# usb-seal.net
KiCad netlist of a schematic drawn in EasyEDA Pro
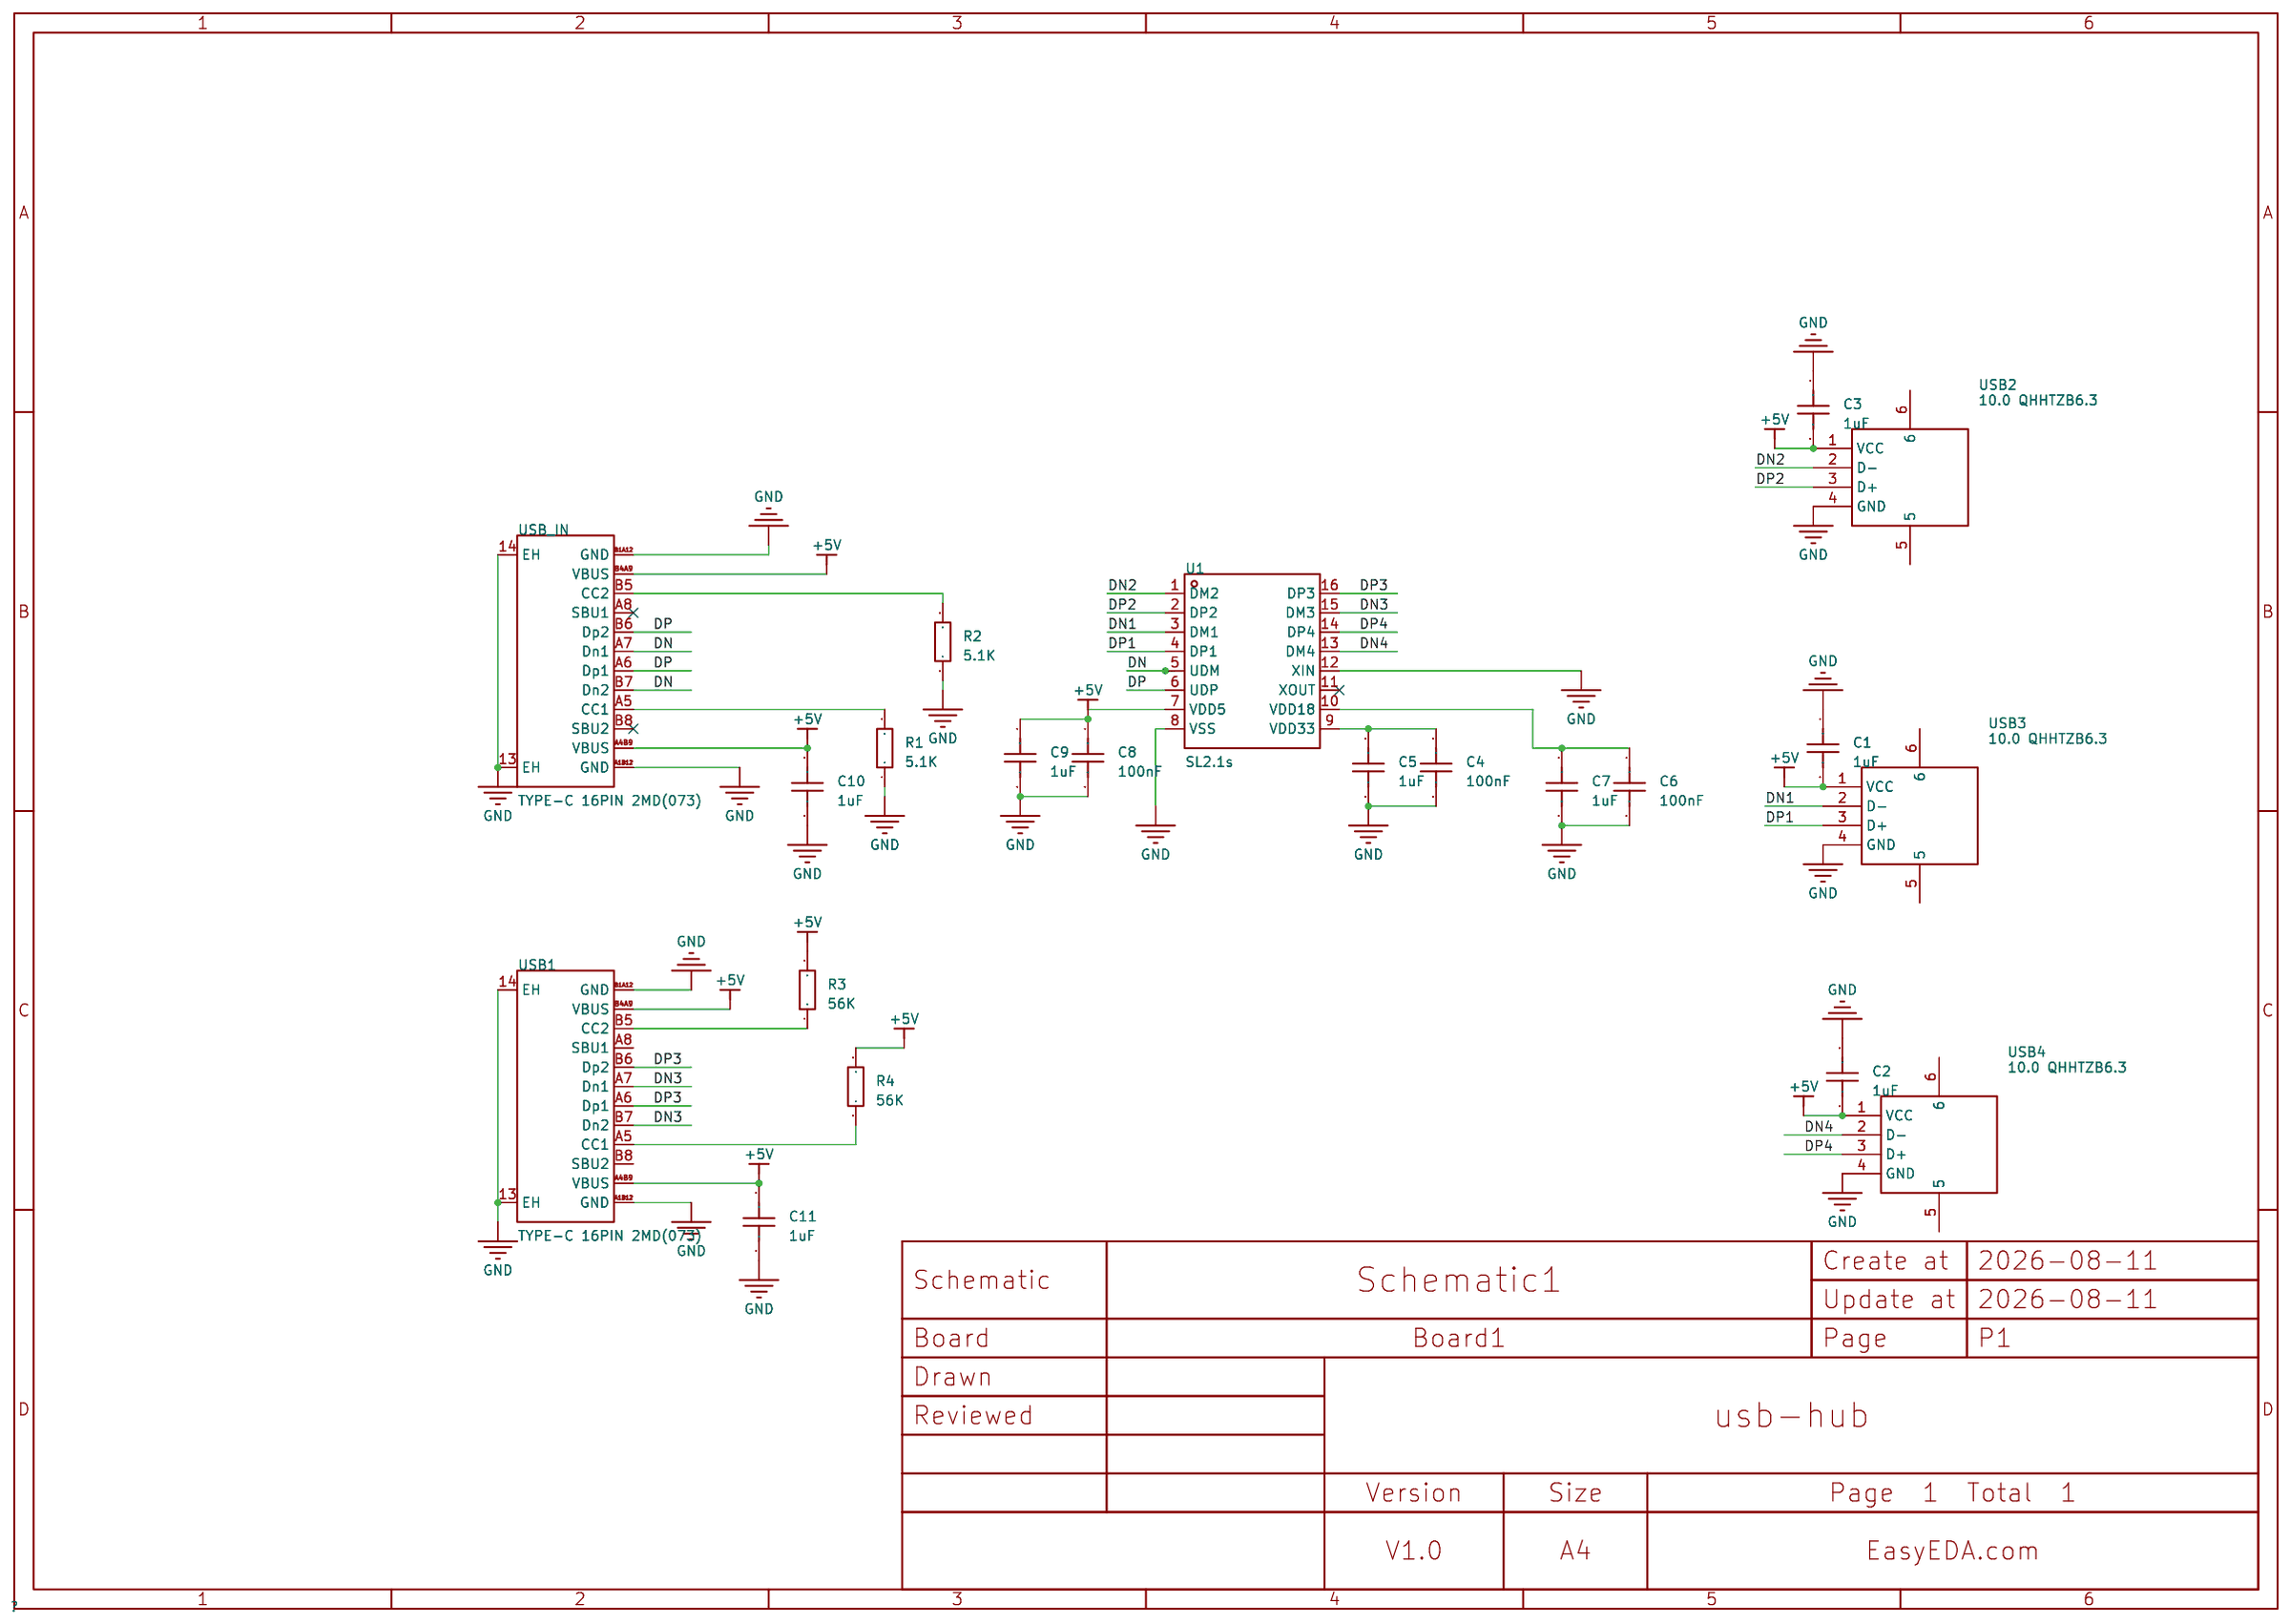
[diagram p0: schematic sheet]

(export (version "E")
  (design (tool "Eeschema 10.0.6"))
  (components
    (comp (ref "C1")
      (value "1uF")
      (footprint "easyedapro:C0603")
      (libsource (lib "easyedapro") (part "CAP_OLD"))
    )
    (comp (ref "C2")
      (value "1uF")
      (footprint "easyedapro:C0603")
      (libsource (lib "easyedapro") (part "CAP_OLD"))
    )
    (comp (ref "C3")
      (value "1uF")
      (footprint "easyedapro:C0603")
      (libsource (lib "easyedapro") (part "CAP_OLD"))
    )
    (comp (ref "C4")
      (value "100nF")
      (footprint "easyedapro:C0603")
      (libsource (lib "easyedapro") (part "CAP_OLD"))
    )
    (comp (ref "C5")
      (value "1uF")
      (footprint "easyedapro:C0603")
      (libsource (lib "easyedapro") (part "CAP_OLD"))
    )
    (comp (ref "C6")
      (value "100nF")
      (footprint "easyedapro:C0603")
      (libsource (lib "easyedapro") (part "CAP_OLD"))
    )
    (comp (ref "C7")
      (value "1uF")
      (footprint "easyedapro:C0603")
      (libsource (lib "easyedapro") (part "CAP_OLD"))
    )
    (comp (ref "C8")
      (value "100nF")
      (footprint "easyedapro:C0603")
      (libsource (lib "easyedapro") (part "CAP_OLD"))
    )
    (comp (ref "C9")
      (value "1uF")
      (footprint "easyedapro:C0603")
      (libsource (lib "easyedapro") (part "CAP_OLD"))
    )
    (comp (ref "C10")
      (value "1uF")
      (footprint "easyedapro:C0603")
      (libsource (lib "easyedapro") (part "CAP_OLD"))
    )
    (comp (ref "C11")
      (value "1uF")
      (footprint "easyedapro:C0603")
      (libsource (lib "easyedapro") (part "CAP_OLD"))
    )
    (comp (ref "R1")
      (value "5.1K")
      (footprint "easyedapro:R0603")
      (libsource (lib "easyedapro") (part "Res"))
    )
    (comp (ref "R2")
      (value "5.1K")
      (footprint "easyedapro:R0603")
      (libsource (lib "easyedapro") (part "Res"))
    )
    (comp (ref "R3") (value "56K") (footprint "easyedapro:R0603") (libsource (lib "easyedapro") (part "Res")))
    (comp (ref "R4") (value "56K") (footprint "easyedapro:R0603") (libsource (lib "easyedapro") (part "Res")))
    (comp (ref "U1")
      (value "SL2.1s")
      (footprint "easyedapro:SSOP-16_L4.6-W2.6-P0.53-LS4.0-BL")
      (fields (field (name "Manufacturer") "CoreChips(和芯润德)"))
      (libsource (lib "easyedapro") (part "SL2.1S"))
    )
    (comp (ref "USB1")
      (value "TYPE-C 16PIN 2MD(073)")
      (footprint "easyedapro:USB-C-SMD_TYPE-C-16PIN-2MD-073")
      (fields (field (name "Manufacturer") "SHOU HAN(首韩)"))
      (libsource (lib "easyedapro") (part "TYPE-C 16PIN 2MD(073)"))
    )
    (comp (ref "USB2")
      (value "10.0 QHHTZB6.3")
      (footprint "easyedapro:USB-A-TH_10.0QHHTZB6.3")
      (fields (field (name "Manufacturer") "SHOU HAN(首韩)"))
      (libsource (lib "easyedapro") (part "10.0 QHHTZB6.3"))
    )
    (comp (ref "USB3")
      (value "10.0 QHHTZB6.3")
      (footprint "easyedapro:USB-A-TH_10.0QHHTZB6.3")
      (fields (field (name "Manufacturer") "SHOU HAN(首韩)"))
      (libsource (lib "easyedapro") (part "10.0 QHHTZB6.3"))
    )
    (comp (ref "USB4")
      (value "10.0 QHHTZB6.3")
      (footprint "easyedapro:USB-A-TH_10.0QHHTZB6.3")
      (fields (field (name "Manufacturer") "SHOU HAN(首韩)"))
      (libsource (lib "easyedapro") (part "10.0 QHHTZB6.3"))
    )
    (comp (ref "USB_IN")
      (value "TYPE-C 16PIN 2MD(073)")
      (footprint "easyedapro:USB-C-SMD_TYPE-C-16PIN-2MD-073")
      (fields (field (name "Manufacturer") "SHOU HAN(首韩)"))
      (libsource (lib "easyedapro") (part "TYPE-C 16PIN 2MD(073)"))
    )
  )
  (nets
    (net (code "1") (name "+5V") (class "Default")
      (node (ref "C1") (pin "2") (pinfunction "2_2") (pintype "input"))
      (node (ref "C10") (pin "2") (pinfunction "2_2") (pintype "input"))
      (node (ref "C11") (pin "2") (pinfunction "2_2") (pintype "input"))
      (node (ref "C2") (pin "2") (pinfunction "2_2") (pintype "input"))
      (node (ref "C3") (pin "2") (pinfunction "2_2") (pintype "input"))
      (node (ref "C8") (pin "1") (pinfunction "1_1") (pintype "input"))
      (node (ref "C9") (pin "1") (pinfunction "1_1") (pintype "input"))
      (node (ref "R3") (pin "2") (pinfunction "2_2") (pintype "input"))
      (node (ref "R4") (pin "2") (pinfunction "2_2") (pintype "input"))
      (node (ref "U1") (pin "7") (pinfunction "VDD5_7") (pintype "unspecified"))
      (node (ref "USB1") (pin "A4B9") (pinfunction "VBUS_A4B9") (pintype "unspecified"))
      (node (ref "USB1") (pin "B4A9") (pinfunction "VBUS_B4A9") (pintype "unspecified"))
      (node (ref "USB2") (pin "1") (pinfunction "VCC_1") (pintype "unspecified"))
      (node (ref "USB3") (pin "1") (pinfunction "VCC_1") (pintype "unspecified"))
      (node (ref "USB4") (pin "1") (pinfunction "VCC_1") (pintype "unspecified"))
      (node (ref "USB_IN") (pin "A4B9") (pinfunction "VBUS_A4B9") (pintype "unspecified"))
      (node (ref "USB_IN") (pin "B4A9") (pinfunction "VBUS_B4A9") (pintype "unspecified"))
    )
    (net (code "2") (name "/DN") (class "Default")
      (node (ref "U1") (pin "5") (pinfunction "UDM_5") (pintype "unspecified"))
      (node (ref "USB_IN") (pin "A7") (pinfunction "Dn1_A7") (pintype "unspecified"))
      (node (ref "USB_IN") (pin "B7") (pinfunction "Dn2_B7") (pintype "unspecified"))
    )
    (net (code "3") (name "/DN1") (class "Default")
      (node (ref "U1") (pin "3") (pinfunction "DM1_3") (pintype "unspecified"))
      (node (ref "USB3") (pin "2") (pinfunction "D-_2") (pintype "unspecified"))
    )
    (net (code "4") (name "/DN2") (class "Default")
      (node (ref "U1") (pin "1") (pinfunction "DM2_1") (pintype "unspecified"))
      (node (ref "USB2") (pin "2") (pinfunction "D-_2") (pintype "unspecified"))
    )
    (net (code "5") (name "/DN3") (class "Default")
      (node (ref "U1") (pin "15") (pinfunction "DM3_15") (pintype "unspecified"))
      (node (ref "USB1") (pin "A7") (pinfunction "Dn1_A7") (pintype "unspecified"))
      (node (ref "USB1") (pin "B7") (pinfunction "Dn2_B7") (pintype "unspecified"))
    )
    (net (code "6") (name "/DN4") (class "Default")
      (node (ref "U1") (pin "13") (pinfunction "DM4_13") (pintype "unspecified"))
      (node (ref "USB4") (pin "2") (pinfunction "D-_2") (pintype "unspecified"))
    )
    (net (code "7") (name "/DP") (class "Default")
      (node (ref "U1") (pin "6") (pinfunction "UDP_6") (pintype "unspecified"))
      (node (ref "USB_IN") (pin "A6") (pinfunction "Dp1_A6") (pintype "unspecified"))
      (node (ref "USB_IN") (pin "B6") (pinfunction "Dp2_B6") (pintype "unspecified"))
    )
    (net (code "8") (name "/DP1") (class "Default")
      (node (ref "U1") (pin "4") (pinfunction "DP1_4") (pintype "unspecified"))
      (node (ref "USB3") (pin "3") (pinfunction "D+_3") (pintype "unspecified"))
    )
    (net (code "9") (name "/DP2") (class "Default")
      (node (ref "U1") (pin "2") (pinfunction "DP2_2") (pintype "unspecified"))
      (node (ref "USB2") (pin "3") (pinfunction "D+_3") (pintype "unspecified"))
    )
    (net (code "10") (name "/DP3") (class "Default")
      (node (ref "U1") (pin "16") (pinfunction "DP3_16") (pintype "unspecified"))
      (node (ref "USB1") (pin "A6") (pinfunction "Dp1_A6") (pintype "unspecified"))
      (node (ref "USB1") (pin "B6") (pinfunction "Dp2_B6") (pintype "unspecified"))
    )
    (net (code "11") (name "/DP4") (class "Default")
      (node (ref "U1") (pin "14") (pinfunction "DP4_14") (pintype "unspecified"))
      (node (ref "USB4") (pin "3") (pinfunction "D+_3") (pintype "unspecified"))
    )
    (net (code "12") (name "GND") (class "Default")
      (node (ref "C1") (pin "1") (pinfunction "1_1") (pintype "input"))
      (node (ref "C10") (pin "1") (pinfunction "1_1") (pintype "input"))
      (node (ref "C11") (pin "1") (pinfunction "1_1") (pintype "input"))
      (node (ref "C2") (pin "1") (pinfunction "1_1") (pintype "input"))
      (node (ref "C3") (pin "1") (pinfunction "1_1") (pintype "input"))
      (node (ref "C4") (pin "2") (pinfunction "2_2") (pintype "input"))
      (node (ref "C5") (pin "2") (pinfunction "2_2") (pintype "input"))
      (node (ref "C6") (pin "2") (pinfunction "2_2") (pintype "input"))
      (node (ref "C7") (pin "2") (pinfunction "2_2") (pintype "input"))
      (node (ref "C8") (pin "2") (pinfunction "2_2") (pintype "input"))
      (node (ref "C9") (pin "2") (pinfunction "2_2") (pintype "input"))
      (node (ref "R1") (pin "1") (pinfunction "1_1") (pintype "input"))
      (node (ref "R2") (pin "1") (pinfunction "1_1") (pintype "input"))
      (node (ref "U1") (pin "12") (pinfunction "XIN_12") (pintype "unspecified"))
      (node (ref "U1") (pin "8") (pinfunction "VSS_8") (pintype "unspecified"))
      (node (ref "USB1") (pin "13") (pinfunction "EH_13") (pintype "unspecified"))
      (node (ref "USB1") (pin "14") (pinfunction "EH_14") (pintype "unspecified"))
      (node (ref "USB1") (pin "A1B12") (pinfunction "GND_A1B12") (pintype "unspecified"))
      (node (ref "USB1") (pin "B1A12") (pinfunction "GND_B1A12") (pintype "unspecified"))
      (node (ref "USB2") (pin "4") (pinfunction "GND_4") (pintype "unspecified"))
      (node (ref "USB3") (pin "4") (pinfunction "GND_4") (pintype "unspecified"))
      (node (ref "USB4") (pin "4") (pinfunction "GND_4") (pintype "unspecified"))
      (node (ref "USB_IN") (pin "13") (pinfunction "EH_13") (pintype "unspecified"))
      (node (ref "USB_IN") (pin "14") (pinfunction "EH_14") (pintype "unspecified"))
      (node (ref "USB_IN") (pin "A1B12") (pinfunction "GND_A1B12") (pintype "unspecified"))
      (node (ref "USB_IN") (pin "B1A12") (pinfunction "GND_B1A12") (pintype "unspecified"))
    )
    (net (code "13") (name "Net-(U1-VDD18)") (class "Default")
      (node (ref "C6") (pin "1") (pinfunction "1_1") (pintype "input"))
      (node (ref "C7") (pin "1") (pinfunction "1_1") (pintype "input"))
      (node (ref "U1") (pin "10") (pinfunction "VDD18_10") (pintype "unspecified"))
    )
    (net (code "14") (name "Net-(U1-VDD33)") (class "Default")
      (node (ref "C4") (pin "1") (pinfunction "1_1") (pintype "input"))
      (node (ref "C5") (pin "1") (pinfunction "1_1") (pintype "input"))
      (node (ref "U1") (pin "9") (pinfunction "VDD33_9") (pintype "unspecified"))
    )
    (net (code "15") (name "Net-(USB1-CC1)") (class "Default")
      (node (ref "R4") (pin "1") (pinfunction "1_1") (pintype "input"))
      (node (ref "USB1") (pin "A5") (pinfunction "CC1_A5") (pintype "unspecified"))
    )
    (net (code "16") (name "Net-(USB1-CC2)") (class "Default")
      (node (ref "R3") (pin "1") (pinfunction "1_1") (pintype "input"))
      (node (ref "USB1") (pin "B5") (pinfunction "CC2_B5") (pintype "unspecified"))
    )
    (net (code "17") (name "Net-(USB_IN-CC1)") (class "Default")
      (node (ref "R1") (pin "2") (pinfunction "2_2") (pintype "input"))
      (node (ref "USB_IN") (pin "A5") (pinfunction "CC1_A5") (pintype "unspecified"))
    )
    (net (code "18") (name "Net-(USB_IN-CC2)") (class "Default")
      (node (ref "R2") (pin "2") (pinfunction "2_2") (pintype "input"))
      (node (ref "USB_IN") (pin "B5") (pinfunction "CC2_B5") (pintype "unspecified"))
    )
    (net (code "19") (name "unconnected-(U1-XOUT-Pad11)") (class "Default")
      (node (ref "U1") (pin "11") (pinfunction "XOUT_11") (pintype "unspecified+no_connect"))
    )
    (net (code "20") (name "unconnected-(USB1-SBU1-PadA8)") (class "Default")
      (node (ref "USB1") (pin "A8") (pinfunction "SBU1_A8") (pintype "unspecified"))
    )
    (net (code "21") (name "unconnected-(USB1-SBU2-PadB8)") (class "Default")
      (node (ref "USB1") (pin "B8") (pinfunction "SBU2_B8") (pintype "unspecified"))
    )
    (net (code "22") (name "unconnected-(USB2-Pad5)") (class "Default")
      (node (ref "USB2") (pin "5") (pinfunction "5_5") (pintype "unspecified"))
    )
    (net (code "23") (name "unconnected-(USB2-Pad6)") (class "Default")
      (node (ref "USB2") (pin "6") (pinfunction "6_6") (pintype "unspecified"))
    )
    (net (code "24") (name "unconnected-(USB3-Pad5)") (class "Default")
      (node (ref "USB3") (pin "5") (pinfunction "5_5") (pintype "unspecified"))
    )
    (net (code "25") (name "unconnected-(USB3-Pad6)") (class "Default")
      (node (ref "USB3") (pin "6") (pinfunction "6_6") (pintype "unspecified"))
    )
    (net (code "26") (name "unconnected-(USB4-Pad5)") (class "Default")
      (node (ref "USB4") (pin "5") (pinfunction "5_5") (pintype "unspecified"))
    )
    (net (code "27") (name "unconnected-(USB4-Pad6)") (class "Default")
      (node (ref "USB4") (pin "6") (pinfunction "6_6") (pintype "unspecified"))
    )
    (net (code "28") (name "unconnected-(USB_IN-SBU1-PadA8)") (class "Default")
      (node (ref "USB_IN") (pin "A8") (pinfunction "SBU1_A8") (pintype "unspecified+no_connect"))
    )
    (net (code "29") (name "unconnected-(USB_IN-SBU2-PadB8)") (class "Default")
      (node (ref "USB_IN") (pin "B8") (pinfunction "SBU2_B8") (pintype "unspecified+no_connect"))
    )
  )
)
